# IC555_FLOW_RELAY_MOTTOR.net
KiCad netlist of a schematic drawn in Altium Designer
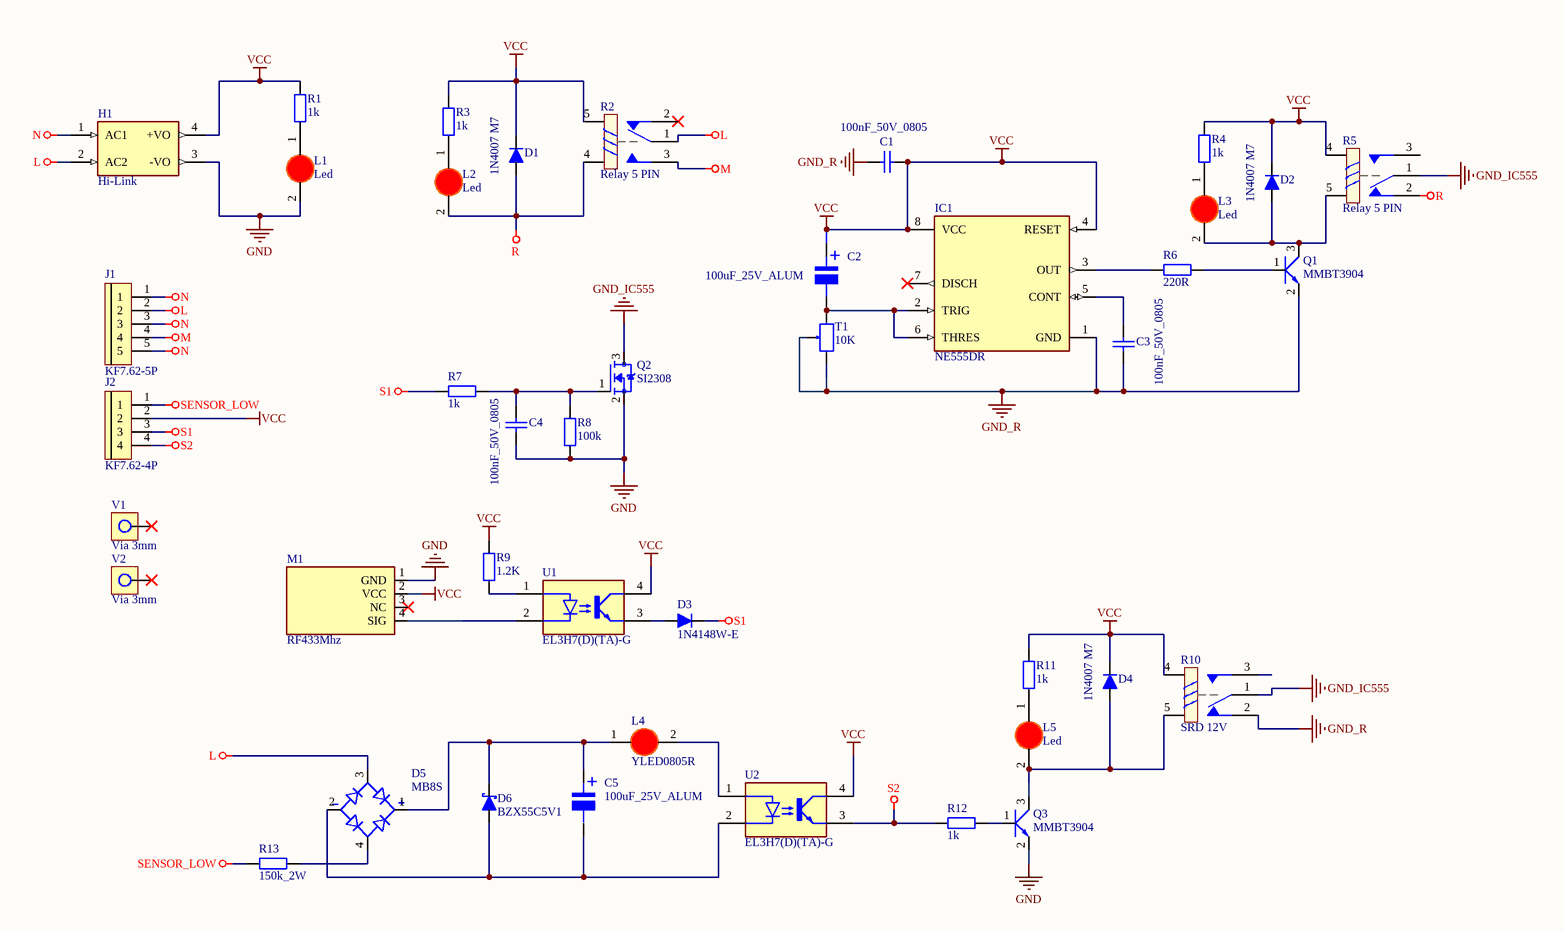
[diagram p0: IC555_FLOW_RELAY_MOTTOR.SchDoc]

(export (version "E")
  (design (tool "Eeschema 10.0.6"))
  (components
    (comp (ref "C1")
      (value "100nF_50V_0805")
      (footprint "Capitor 0805")
      (fields (field (name "MANUFACTURER") "YAGEO") (field (name "PART NUMBER") "CC0805KRX7R9BB104"))
      (libsource (lib "My_Lib") (part "100nF_50V_0805"))
    )
    (comp (ref "C2")
      (value "100uF_25V_ALUM")
      (footprint "CAPITOR D6.3 x L7.7mm (D)")
      (description "SMD")
      (fields (field (name "MANUFACTURER") "KNSCHA") (field (name "PART NUMBER") "RVT100UF25V67RV0011"))
      (libsource (lib "My_Lib") (part "100uF_25V_ALUM"))
    )
    (comp (ref "C3")
      (value "100nF_50V_0805")
      (footprint "Capitor 0805")
      (fields (field (name "MANUFACTURER") "YAGEO") (field (name "PART NUMBER") "CC0805KRX7R9BB104"))
      (libsource (lib "My_Lib") (part "100nF_50V_0805"))
    )
    (comp (ref "C4")
      (value "100nF_50V_0805")
      (footprint "Capitor 0805")
      (fields (field (name "MANUFACTURER") "YAGEO") (field (name "PART NUMBER") "CC0805KRX7R9BB104"))
      (libsource (lib "My_Lib") (part "100nF_50V_0805"))
    )
    (comp (ref "C5")
      (value "100uF_25V_ALUM")
      (footprint "tu nhom 6.3 (d)")
      (description "Dán")
      (libsource (lib "Altium_Lib_by_KhueNguyenCreator") (part "Tu Nhom 100uF 25V"))
    )
    (comp (ref "D1")
      (value "1N4007 M7")
      (footprint "DO-214AC")
      (fields (field (name "MANUFACTURER") "JSMSEMI"))
      (libsource (lib "My_Lib") (part "1N4007 M7"))
    )
    (comp (ref "D2")
      (value "1N4007 M7")
      (footprint "DO-214AC")
      (fields (field (name "MANUFACTURER") "JSMSEMI"))
      (libsource (lib "My_Lib") (part "1N4007 M7"))
    )
    (comp (ref "D3")
      (value "1N4148W-E")
      (footprint "SOD123")
      (fields (field (name "MANUFACTURER") "MDD"))
      (libsource (lib "My_Lib") (part "1N4148W-E"))
    )
    (comp (ref "D4")
      (value "1N4007 M7")
      (footprint "DO-214AC")
      (fields (field (name "MANUFACTURER") "JSMSEMI"))
      (libsource (lib "My_Lib") (part "1N4007 M7"))
    )
    (comp (ref "D5")
      (value "MB8S")
      (footprint "SOIC4W")
      (description "800V 0.5A")
      (fields (field (name "MANUFACTURER") "onsemi"))
      (libsource (lib "My_Lib") (part "MB8S"))
    )
    (comp (ref "D6")
      (value "BZX55C5V1")
      (footprint "DO-35")
      (description "5.1VDC 0.5W")
      (fields (field (name "MANUFACTURER") "LGE"))
      (libsource (lib "My_Lib") (part "BZX55C5V1"))
    )
    (comp (ref "H1") (value "Hi-Link") (footprint "HI-LINK 3W") (libsource (lib "My_Lib") (part "Hi-Link")))
    (comp (ref "IC1") (value "NE555DR") (footprint "8-SOIC") (libsource (lib "My_Lib") (part "NE555DR")))
    (comp (ref "J1")
      (value "KF7.62-5P")
      (footprint "KF7.62 5P")
      (fields (field (name "MANUFACTURER") "Cixi Kefa Elec"))
      (libsource (lib "My_Lib") (part "KF7.62-5P"))
    )
    (comp (ref "J2")
      (value "KF7.62-4P")
      (footprint "KF7.62 4P")
      (fields (field (name "MANUFACTURER") "Cixi Kefa Elec"))
      (libsource (lib "My_Lib") (part "KF7.62-4P"))
    )
    (comp (ref "L1") (value "Led") (footprint "0805") (libsource (lib "My_Lib") (part "Led")))
    (comp (ref "L2") (value "Led") (footprint "0805") (libsource (lib "My_Lib") (part "Led")))
    (comp (ref "L3") (value "Led") (footprint "0805") (libsource (lib "My_Lib") (part "Led")))
    (comp (ref "L4")
      (value "YLED0805R")
      (footprint "YLED0805R")
      (fields (field (name "MANUFACTURER") "YONGYUTAI"))
      (libsource (lib "My_Lib") (part "YLED0805R"))
    )
    (comp (ref "L5") (value "Led") (footprint "0805") (libsource (lib "My_Lib") (part "Led")))
    (comp (ref "M1")
      (value "RF433Mhz")
      (footprint "RF433Mhz 1CH")
      (description "1CH")
      (fields (field (name "MANUFACTURER") "?"))
      (libsource (lib "My_Lib") (part "RF433Mhz"))
    )
    (comp (ref "Q1")
      (value "MMBT3904")
      (footprint "SOT-23")
      (fields (field (name "MANUFACTURER") "GOODWORK") (field (name "PART NUMBER") "2SC1815"))
      (libsource (lib "My_Lib") (part "2SC1815"))
    )
    (comp (ref "Q2")
      (value "SI2308")
      (footprint "SOT-23")
      (fields (field (name "MANUFACTURER") "HXY MOSFET"))
      (libsource (lib "My_Lib") (part "SI2308"))
    )
    (comp (ref "Q3")
      (value "MMBT3904")
      (footprint "SOT-23")
      (fields (field (name "MANUFACTURER") "GOODWORK") (field (name "PART NUMBER") "2SC1815"))
      (libsource (lib "My_Lib") (part "2SC1815"))
    )
    (comp (ref "R1") (value "1k") (footprint "Resistor 0805") (libsource (lib "My_Lib") (part "Res")))
    (comp (ref "R2")
      (value "Relay 5 PIN")
      (footprint "RELAY YL224-A-S 5PIN")
      (fields (field (name "MANUFACTURER") "?"))
      (libsource (lib "") (part "Relay 5 PIN_1"))
    )
    (comp (ref "R3") (value "1k") (footprint "Resistor 0805") (libsource (lib "My_Lib") (part "Res")))
    (comp (ref "R4") (value "1k") (footprint "Resistor 0805") (libsource (lib "My_Lib") (part "Res")))
    (comp (ref "R5")
      (value "Relay 5 PIN")
      (footprint "Relay SRD 5 PIN")
      (fields (field (name "MANUFACTURER") "?"))
      (libsource (lib "My_Lib") (part "Relay 5 PIN"))
    )
    (comp (ref "R6") (value "220R") (footprint "Resistor 0805") (libsource (lib "My_Lib") (part "Res")))
    (comp (ref "R7") (value "1k") (footprint "Resistor 0805") (libsource (lib "My_Lib") (part "Res")))
    (comp (ref "R8") (value "100k") (footprint "Resistor 0805") (libsource (lib "My_Lib") (part "Res")))
    (comp (ref "R9") (value "1.2K") (footprint "Resistor 0805") (libsource (lib "My_Lib") (part "Res")))
    (comp (ref "R10")
      (value "SRD 12V")
      (footprint "Relay SRD 5 PIN")
      (fields (field (name "MANUFACTURER") "?"))
      (libsource (lib "My_Lib") (part "Relay 5 PIN"))
    )
    (comp (ref "R11") (value "1k") (footprint "Resistor 0805") (libsource (lib "My_Lib") (part "Res")))
    (comp (ref "R12") (value "1k") (footprint "Resistor 0805") (libsource (lib "My_Lib") (part "Res")))
    (comp (ref "R13")
      (value "150k_2W")
      (footprint "Resistor DIP 2W TYPE1")
      (fields
        (field (name "MANUFACTURER") "CCO(Chian Chia Elec)")
        (field (name "PART NUMBER") "MOF2WS-150KΩ±5% T")
      )
      (libsource (lib "My_Lib") (part "150k_2W"))
    )
    (comp (ref "T1")
      (value "10K")
      (footprint "Bien Tro Vi Chinh Dung")
      (description "Cắm")
      (libsource (lib "Altium_Lib_by_KhueNguyenCreator") (part "Bien Tro Tinh Chinh 10K Dung"))
    )
    (comp (ref "U1")
      (value "EL3H7(D)(TA)-G")
      (footprint "4-SSOP")
      (fields (field (name "MANUFACTURER") "EVERLIGHT"))
      (libsource (lib "My_Lib") (part "EL3H7(D)(TA)-G"))
    )
    (comp (ref "U2")
      (value "EL3H7(D)(TA)-G")
      (footprint "4-SSOP")
      (fields (field (name "MANUFACTURER") "EVERLIGHT"))
      (libsource (lib "My_Lib") (part "EL3H7(D)(TA)-G"))
    )
    (comp (ref "V1") (value "Via 3mm") (footprint "Via 3mm") (libsource (lib "My_Lib") (part "Via 3mm")))
    (comp (ref "V2") (value "Via 3mm") (footprint "Via 3mm") (libsource (lib "My_Lib") (part "Via 3mm")))
  )
  (nets
    (net (code "1") (name "GND") (class "Default")
      (node (ref "C4") (pin "1") (pinfunction "1_1") (pintype "passive"))
      (node (ref "H1") (pin "3") (pinfunction "-VO_3") (pintype "output"))
      (node (ref "L1") (pin "2") (pinfunction "K_2") (pintype "passive"))
      (node (ref "M1") (pin "1") (pinfunction "GND_1") (pintype "passive"))
      (node (ref "Q2") (pin "2") (pinfunction "S_2") (pintype "passive"))
      (node (ref "Q3") (pin "2") (pinfunction "E_2") (pintype "passive"))
      (node (ref "R8") (pin "1") (pinfunction "1_1") (pintype "passive"))
    )
    (net (code "2") (name "GND_IC555") (class "Default")
      (node (ref "Q2") (pin "3") (pinfunction "D_3") (pintype "passive"))
      (node (ref "R10") (pin "1") (pinfunction "1_1") (pintype "passive"))
      (node (ref "R5") (pin "1") (pinfunction "1_1") (pintype "passive"))
    )
    (net (code "3") (name "GND_R") (class "Default")
      (node (ref "C1") (pin "2") (pinfunction "2_2") (pintype "passive"))
      (node (ref "C3") (pin "2") (pinfunction "2_2") (pintype "passive"))
      (node (ref "IC1") (pin "1") (pinfunction "GND_1") (pintype "power_in"))
      (node (ref "Q1") (pin "2") (pinfunction "E_2") (pintype "passive"))
      (node (ref "R10") (pin "2") (pinfunction "2_2") (pintype "passive"))
      (node (ref "T1") (pin "2") (pinfunction "2_2") (pintype "passive"))
      (node (ref "T1") (pin "3") (pinfunction "3_3") (pintype "passive"))
    )
    (net (code "4") (name "L") (class "Default")
      (node (ref "D5") (pin "3") (pinfunction "AC1_3") (pintype "passive"))
      (node (ref "H1") (pin "2") (pinfunction "AC2_2") (pintype "input"))
      (node (ref "J1") (pin "2") (pinfunction "2_2") (pintype "passive"))
      (node (ref "R2") (pin "1") (pinfunction "1_1") (pintype "passive"))
    )
    (net (code "5") (name "M") (class "Default")
      (node (ref "J1") (pin "4") (pinfunction "4_4") (pintype "passive"))
      (node (ref "R2") (pin "3") (pinfunction "3_3") (pintype "passive"))
    )
    (net (code "6") (name "N") (class "Default")
      (node (ref "H1") (pin "1") (pinfunction "AC1_1") (pintype "input"))
      (node (ref "J1") (pin "1") (pinfunction "1_1") (pintype "passive"))
      (node (ref "J1") (pin "3") (pinfunction "3_3") (pintype "passive"))
      (node (ref "J1") (pin "5") (pinfunction "5_5") (pintype "passive"))
    )
    (net (code "7") (name "Net-(D5-AC2)") (class "Default")
      (node (ref "D5") (pin "4") (pinfunction "AC2_4") (pintype "passive"))
      (node (ref "R13") (pin "2") (pinfunction "2_2") (pintype "passive"))
    )
    (net (code "8") (name "Net-(D5-NEG)") (class "Default")
      (node (ref "C5") (pin "2") (pinfunction "2_2") (pintype "passive"))
      (node (ref "D5") (pin "2") (pinfunction "NEG_2") (pintype "passive"))
      (node (ref "D6") (pin "A") (pinfunction "A_A") (pintype "passive"))
      (node (ref "U2") (pin "2") (pinfunction "C_2") (pintype "passive"))
    )
    (net (code "9") (name "Net-(D5-POS)") (class "Default")
      (node (ref "C5") (pin "1") (pinfunction "1_1") (pintype "passive"))
      (node (ref "D5") (pin "1") (pinfunction "POS_1") (pintype "passive"))
      (node (ref "D6") (pin "C") (pinfunction "K_C") (pintype "passive"))
      (node (ref "L4") (pin "1") (pinfunction "A_1") (pintype "passive"))
    )
    (net (code "10") (name "Net-(IC1-CONT)") (class "Default")
      (node (ref "C3") (pin "1") (pinfunction "1_1") (pintype "passive"))
      (node (ref "IC1") (pin "5") (pinfunction "CONT_5") (pintype "bidirectional"))
    )
    (net (code "11") (name "Net-(IC1-OUT)") (class "Default")
      (node (ref "IC1") (pin "3") (pinfunction "OUT_3") (pintype "output"))
      (node (ref "R6") (pin "1") (pinfunction "1_1") (pintype "passive"))
    )
    (net (code "12") (name "Net-(IC1-THRES)") (class "Default")
      (node (ref "C2") (pin "2") (pinfunction "2_2") (pintype "passive"))
      (node (ref "IC1") (pin "2") (pinfunction "TRIG_2") (pintype "input"))
      (node (ref "IC1") (pin "6") (pinfunction "THRES_6") (pintype "input"))
      (node (ref "T1") (pin "1") (pinfunction "1_1") (pintype "passive"))
    )
    (net (code "13") (name "Net-(L1-A)") (class "Default")
      (node (ref "L1") (pin "1") (pinfunction "A_1") (pintype "passive"))
      (node (ref "R1") (pin "2") (pinfunction "2_2") (pintype "passive"))
    )
    (net (code "14") (name "Net-(L2-A)") (class "Default")
      (node (ref "L2") (pin "1") (pinfunction "A_1") (pintype "passive"))
      (node (ref "R3") (pin "2") (pinfunction "2_2") (pintype "passive"))
    )
    (net (code "15") (name "Net-(L3-A)") (class "Default")
      (node (ref "L3") (pin "1") (pinfunction "A_1") (pintype "passive"))
      (node (ref "R4") (pin "2") (pinfunction "2_2") (pintype "passive"))
    )
    (net (code "16") (name "Net-(L3-K)") (class "Default")
      (node (ref "D2") (pin "A") (pinfunction "A_A") (pintype "passive"))
      (node (ref "L3") (pin "2") (pinfunction "K_2") (pintype "passive"))
      (node (ref "Q1") (pin "3") (pinfunction "C_3") (pintype "passive"))
      (node (ref "R5") (pin "5") (pinfunction "5_5") (pintype "passive"))
    )
    (net (code "17") (name "Net-(L4-K)") (class "Default")
      (node (ref "L4") (pin "2") (pinfunction "K_2") (pintype "passive"))
      (node (ref "U2") (pin "1") (pinfunction "A_1") (pintype "passive"))
    )
    (net (code "18") (name "Net-(L5-A)") (class "Default")
      (node (ref "L5") (pin "1") (pinfunction "A_1") (pintype "passive"))
      (node (ref "R11") (pin "2") (pinfunction "2_2") (pintype "passive"))
    )
    (net (code "19") (name "Net-(L5-K)") (class "Default")
      (node (ref "D4") (pin "A") (pinfunction "A_A") (pintype "passive"))
      (node (ref "L5") (pin "2") (pinfunction "K_2") (pintype "passive"))
      (node (ref "Q3") (pin "3") (pinfunction "C_3") (pintype "passive"))
      (node (ref "R10") (pin "5") (pinfunction "5_5") (pintype "passive"))
    )
    (net (code "20") (name "Net-(M1-SIG)") (class "Default")
      (node (ref "M1") (pin "4") (pinfunction "SIG_4") (pintype "passive"))
      (node (ref "U1") (pin "2") (pinfunction "C_2") (pintype "passive"))
    )
    (net (code "21") (name "Net-(Q1-B)") (class "Default")
      (node (ref "Q1") (pin "1") (pinfunction "B_1") (pintype "passive"))
      (node (ref "R6") (pin "2") (pinfunction "2_2") (pintype "passive"))
    )
    (net (code "22") (name "Net-(Q2-G)") (class "Default")
      (node (ref "C4") (pin "2") (pinfunction "2_2") (pintype "passive"))
      (node (ref "Q2") (pin "1") (pinfunction "G_1") (pintype "passive"))
      (node (ref "R7") (pin "2") (pinfunction "2_2") (pintype "passive"))
      (node (ref "R8") (pin "2") (pinfunction "2_2") (pintype "passive"))
    )
    (net (code "23") (name "Net-(Q3-B)") (class "Default")
      (node (ref "Q3") (pin "1") (pinfunction "B_1") (pintype "passive"))
      (node (ref "R12") (pin "2") (pinfunction "2_2") (pintype "passive"))
    )
    (net (code "24") (name "Net-(U1-A)") (class "Default")
      (node (ref "R9") (pin "2") (pinfunction "2_2") (pintype "passive"))
      (node (ref "U1") (pin "1") (pinfunction "A_1") (pintype "passive"))
    )
    (net (code "25") (name "Net-(U1-E)") (class "Default")
      (node (ref "D3") (pin "A") (pinfunction "A_A") (pintype "passive"))
      (node (ref "U1") (pin "3") (pinfunction "E_3") (pintype "passive"))
    )
    (net (code "26") (name "R") (class "Default")
      (node (ref "D1") (pin "A") (pinfunction "A_A") (pintype "passive"))
      (node (ref "L2") (pin "2") (pinfunction "K_2") (pintype "passive"))
      (node (ref "R2") (pin "4") (pinfunction "4_4") (pintype "passive"))
      (node (ref "R5") (pin "2") (pinfunction "2_2") (pintype "passive"))
    )
    (net (code "27") (name "S1") (class "Default")
      (node (ref "D3") (pin "C") (pinfunction "K_C") (pintype "passive"))
      (node (ref "J2") (pin "3") (pinfunction "3_3") (pintype "passive"))
      (node (ref "R7") (pin "1") (pinfunction "1_1") (pintype "passive"))
    )
    (net (code "28") (name "S2") (class "Default")
      (node (ref "J2") (pin "4") (pinfunction "4_4") (pintype "passive"))
      (node (ref "R12") (pin "1") (pinfunction "1_1") (pintype "passive"))
      (node (ref "U2") (pin "3") (pinfunction "E_3") (pintype "passive"))
    )
    (net (code "29") (name "SENSOR_LOW") (class "Default")
      (node (ref "J2") (pin "1") (pinfunction "1_1") (pintype "passive"))
      (node (ref "R13") (pin "1") (pinfunction "1_1") (pintype "passive"))
    )
    (net (code "30") (name "VCC") (class "Default")
      (node (ref "C1") (pin "1") (pinfunction "1_1") (pintype "passive"))
      (node (ref "C2") (pin "1") (pinfunction "1_1") (pintype "passive"))
      (node (ref "D1") (pin "C") (pinfunction "K_C") (pintype "passive"))
      (node (ref "D2") (pin "C") (pinfunction "K_C") (pintype "passive"))
      (node (ref "D4") (pin "C") (pinfunction "K_C") (pintype "passive"))
      (node (ref "H1") (pin "4") (pinfunction "+VO_4") (pintype "output"))
      (node (ref "IC1") (pin "4") (pinfunction "RESET_4") (pintype "input"))
      (node (ref "IC1") (pin "8") (pinfunction "VCC_8") (pintype "power_in"))
      (node (ref "J2") (pin "2") (pinfunction "2_2") (pintype "passive"))
      (node (ref "M1") (pin "2") (pinfunction "VCC_2") (pintype "passive"))
      (node (ref "R1") (pin "1") (pinfunction "1_1") (pintype "passive"))
      (node (ref "R10") (pin "4") (pinfunction "4_4") (pintype "passive"))
      (node (ref "R11") (pin "1") (pinfunction "1_1") (pintype "passive"))
      (node (ref "R2") (pin "5") (pinfunction "5_5") (pintype "passive"))
      (node (ref "R3") (pin "1") (pinfunction "1_1") (pintype "passive"))
      (node (ref "R4") (pin "1") (pinfunction "1_1") (pintype "passive"))
      (node (ref "R5") (pin "4") (pinfunction "4_4") (pintype "passive"))
      (node (ref "R9") (pin "1") (pinfunction "1_1") (pintype "passive"))
      (node (ref "U1") (pin "4") (pinfunction "CO_4") (pintype "passive"))
      (node (ref "U2") (pin "4") (pinfunction "CO_4") (pintype "passive"))
    )
    (net (code "31") (name "unconnected-(IC1-DISCH-Pad7)") (class "Default")
      (node (ref "IC1") (pin "7") (pinfunction "DISCH_7") (pintype "output+no_connect"))
    )
    (net (code "32") (name "unconnected-(M1-NC-Pad3)") (class "Default")
      (node (ref "M1") (pin "3") (pinfunction "NC_3") (pintype "passive+no_connect"))
    )
    (net (code "33") (name "unconnected-(R2-Pad2)") (class "Default")
      (node (ref "R2") (pin "2") (pinfunction "2_2") (pintype "passive+no_connect"))
    )
    (net (code "34") (name "unconnected-(R5-Pad3)") (class "Default")
      (node (ref "R5") (pin "3") (pinfunction "3_3") (pintype "passive"))
    )
    (net (code "35") (name "unconnected-(R10-Pad3)") (class "Default")
      (node (ref "R10") (pin "3") (pinfunction "3_3") (pintype "passive"))
    )
    (net (code "36") (name "unconnected-(V1-Pad1)") (class "Default")
      (node (ref "V1") (pin "1") (pinfunction "1_1") (pintype "passive+no_connect"))
    )
    (net (code "37") (name "unconnected-(V2-Pad1)") (class "Default")
      (node (ref "V2") (pin "1") (pinfunction "1_1") (pintype "passive+no_connect"))
    )
  )
)
